# design.net
KiCad netlist of a schematic drawn in Altium Designer
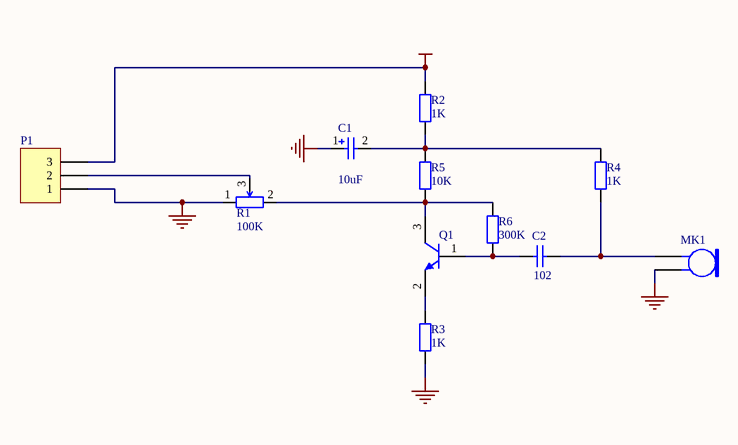
[diagram p0: 输入模块.SchDoc]

(export (version "E")
  (design (tool "Eeschema 10.0.6"))
  (components
    (comp (ref "C1")
      (value "10uF")
      (footprint "zxcourhc:C-DJ-6")
      (description "电解电容")
      (fields (field (name "Comment") "DJDR") (field (name "PUBLISHER") "Altium Limited"))
      (libsource (lib "zxcourhc") (part "DJDR"))
    )
    (comp (ref "C2")
      (value "102")
      (footprint "zxcourhc:TP-0805-R")
      (description "瓷片电容")
      (fields (field (name "Comment") "CPDR") (field (name "PUBLISHER") "Altium Limited"))
      (libsource (lib "zxcourhc") (part "CPDR"))
    )
    (comp (ref "MK1")
      (value "MKF")
      (footprint "zxcourhc:JK128_2")
      (description "麦克风")
      (fields (field (name "PUBLISHER") "Altium Limited"))
      (libsource (lib "zxcourhc") (part "MKF"))
    )
    (comp (ref "P1")
      (value "Header 3")
      (footprint "zxcourhc:HDR-3")
      (description "Header, 3-Pin")
      (fields (field (name "PUBLISHER") "Altium Limited"))
      (libsource (lib "Miscellaneous Connectors") (part "Header 3"))
    )
    (comp (ref "Q1")
      (value "TPSJG_NPN")
      (footprint "BCY-W3/E4")
      (description "贴片三极管——NPN")
      (fields (field (name "PUBLISHER") "Altium Limited"))
      (libsource (lib "zxcourhc") (part "TPSJG_NPN"))
    )
    (comp (ref "R1")
      (value "100K")
      (footprint "zxcourhc:SIP3-D")
      (description "j精调电阻")
      (fields (field (name "Comment") "Res _JT") (field (name "PUBLISHER") "Altium Limited"))
      (libsource (lib "zxcourhc") (part "Res _JT"))
    )
    (comp (ref "R2")
      (value "1K")
      (footprint "zxcourhc:TP-0805-R")
      (description "电阻")
      (fields (field (name "Comment") "Res") (field (name "PUBLISHER") "Altium Limited"))
      (libsource (lib "zxcourhc") (part "Res"))
    )
    (comp (ref "R3")
      (value "1K")
      (footprint "zxcourhc:TP-0805-R")
      (description "电阻")
      (fields (field (name "Comment") "Res") (field (name "PUBLISHER") "Altium Limited"))
      (libsource (lib "zxcourhc") (part "Res"))
    )
    (comp (ref "R4")
      (value "1K")
      (footprint "zxcourhc:TP-0805-R")
      (description "电阻")
      (fields (field (name "Comment") "Res") (field (name "PUBLISHER") "Altium Limited"))
      (libsource (lib "zxcourhc") (part "Res"))
    )
    (comp (ref "R5")
      (value "10K")
      (footprint "zxcourhc:TP-0805-R")
      (description "电阻")
      (fields (field (name "Comment") "Res") (field (name "PUBLISHER") "Altium Limited"))
      (libsource (lib "zxcourhc") (part "Res"))
    )
    (comp (ref "R6")
      (value "300K")
      (footprint "zxcourhc:TP-0805-R")
      (description "电阻")
      (fields (field (name "Comment") "Res") (field (name "PUBLISHER") "Altium Limited"))
      (libsource (lib "zxcourhc") (part "Res"))
    )
  )
  (nets
    (net (code "1") (name "GND") (class "Default")
      (node (ref "C1") (pin "1") (pinfunction "1_1") (pintype "passive"))
      (node (ref "MK1") (pin "2") (pinfunction "2_2") (pintype "passive"))
      (node (ref "P1") (pin "1") (pinfunction "1_1") (pintype "passive"))
      (node (ref "R1") (pin "1") (pinfunction "1_1") (pintype "passive"))
      (node (ref "R3") (pin "1") (pinfunction "1_1") (pintype "passive"))
    )
    (net (code "2") (name "Net-(C1-Pad2)") (class "Default")
      (node (ref "C1") (pin "2") (pinfunction "2_2") (pintype "passive"))
      (node (ref "R2") (pin "1") (pinfunction "1_1") (pintype "passive"))
      (node (ref "R4") (pin "2") (pinfunction "2_2") (pintype "passive"))
      (node (ref "R5") (pin "2") (pinfunction "2_2") (pintype "passive"))
    )
    (net (code "3") (name "Net-(C2-Pad2)") (class "Default")
      (node (ref "C2") (pin "2") (pinfunction "2_2") (pintype "passive"))
      (node (ref "MK1") (pin "1") (pinfunction "1_1") (pintype "passive"))
      (node (ref "R4") (pin "1") (pinfunction "1_1") (pintype "passive"))
    )
    (net (code "4") (name "Net-(P1-Pad2)") (class "Default")
      (node (ref "P1") (pin "2") (pinfunction "2_2") (pintype "passive"))
      (node (ref "R1") (pin "3") (pinfunction "3_3") (pintype "passive"))
    )
    (net (code "5") (name "Net-(Q1-B)") (class "Default")
      (node (ref "C2") (pin "1") (pinfunction "1_1") (pintype "passive"))
      (node (ref "Q1") (pin "1") (pinfunction "B_1") (pintype "passive"))
      (node (ref "R6") (pin "1") (pinfunction "1_1") (pintype "passive"))
    )
    (net (code "6") (name "Net-(Q1-C)") (class "Default")
      (node (ref "Q1") (pin "3") (pinfunction "C_3") (pintype "passive"))
      (node (ref "R1") (pin "2") (pinfunction "2_2") (pintype "passive"))
      (node (ref "R5") (pin "1") (pinfunction "1_1") (pintype "passive"))
      (node (ref "R6") (pin "2") (pinfunction "2_2") (pintype "passive"))
    )
    (net (code "7") (name "Net-(Q1-E)") (class "Default")
      (node (ref "Q1") (pin "2") (pinfunction "E_2") (pintype "passive"))
      (node (ref "R3") (pin "2") (pinfunction "2_2") (pintype "passive"))
    )
    (net (code "8") (name "VCC") (class "Default")
      (node (ref "P1") (pin "3") (pinfunction "3_3") (pintype "passive"))
      (node (ref "R2") (pin "2") (pinfunction "2_2") (pintype "passive"))
    )
  )
)
